# Fastino_FPGA.net
KiCad netlist of a schematic drawn in Altium Designer
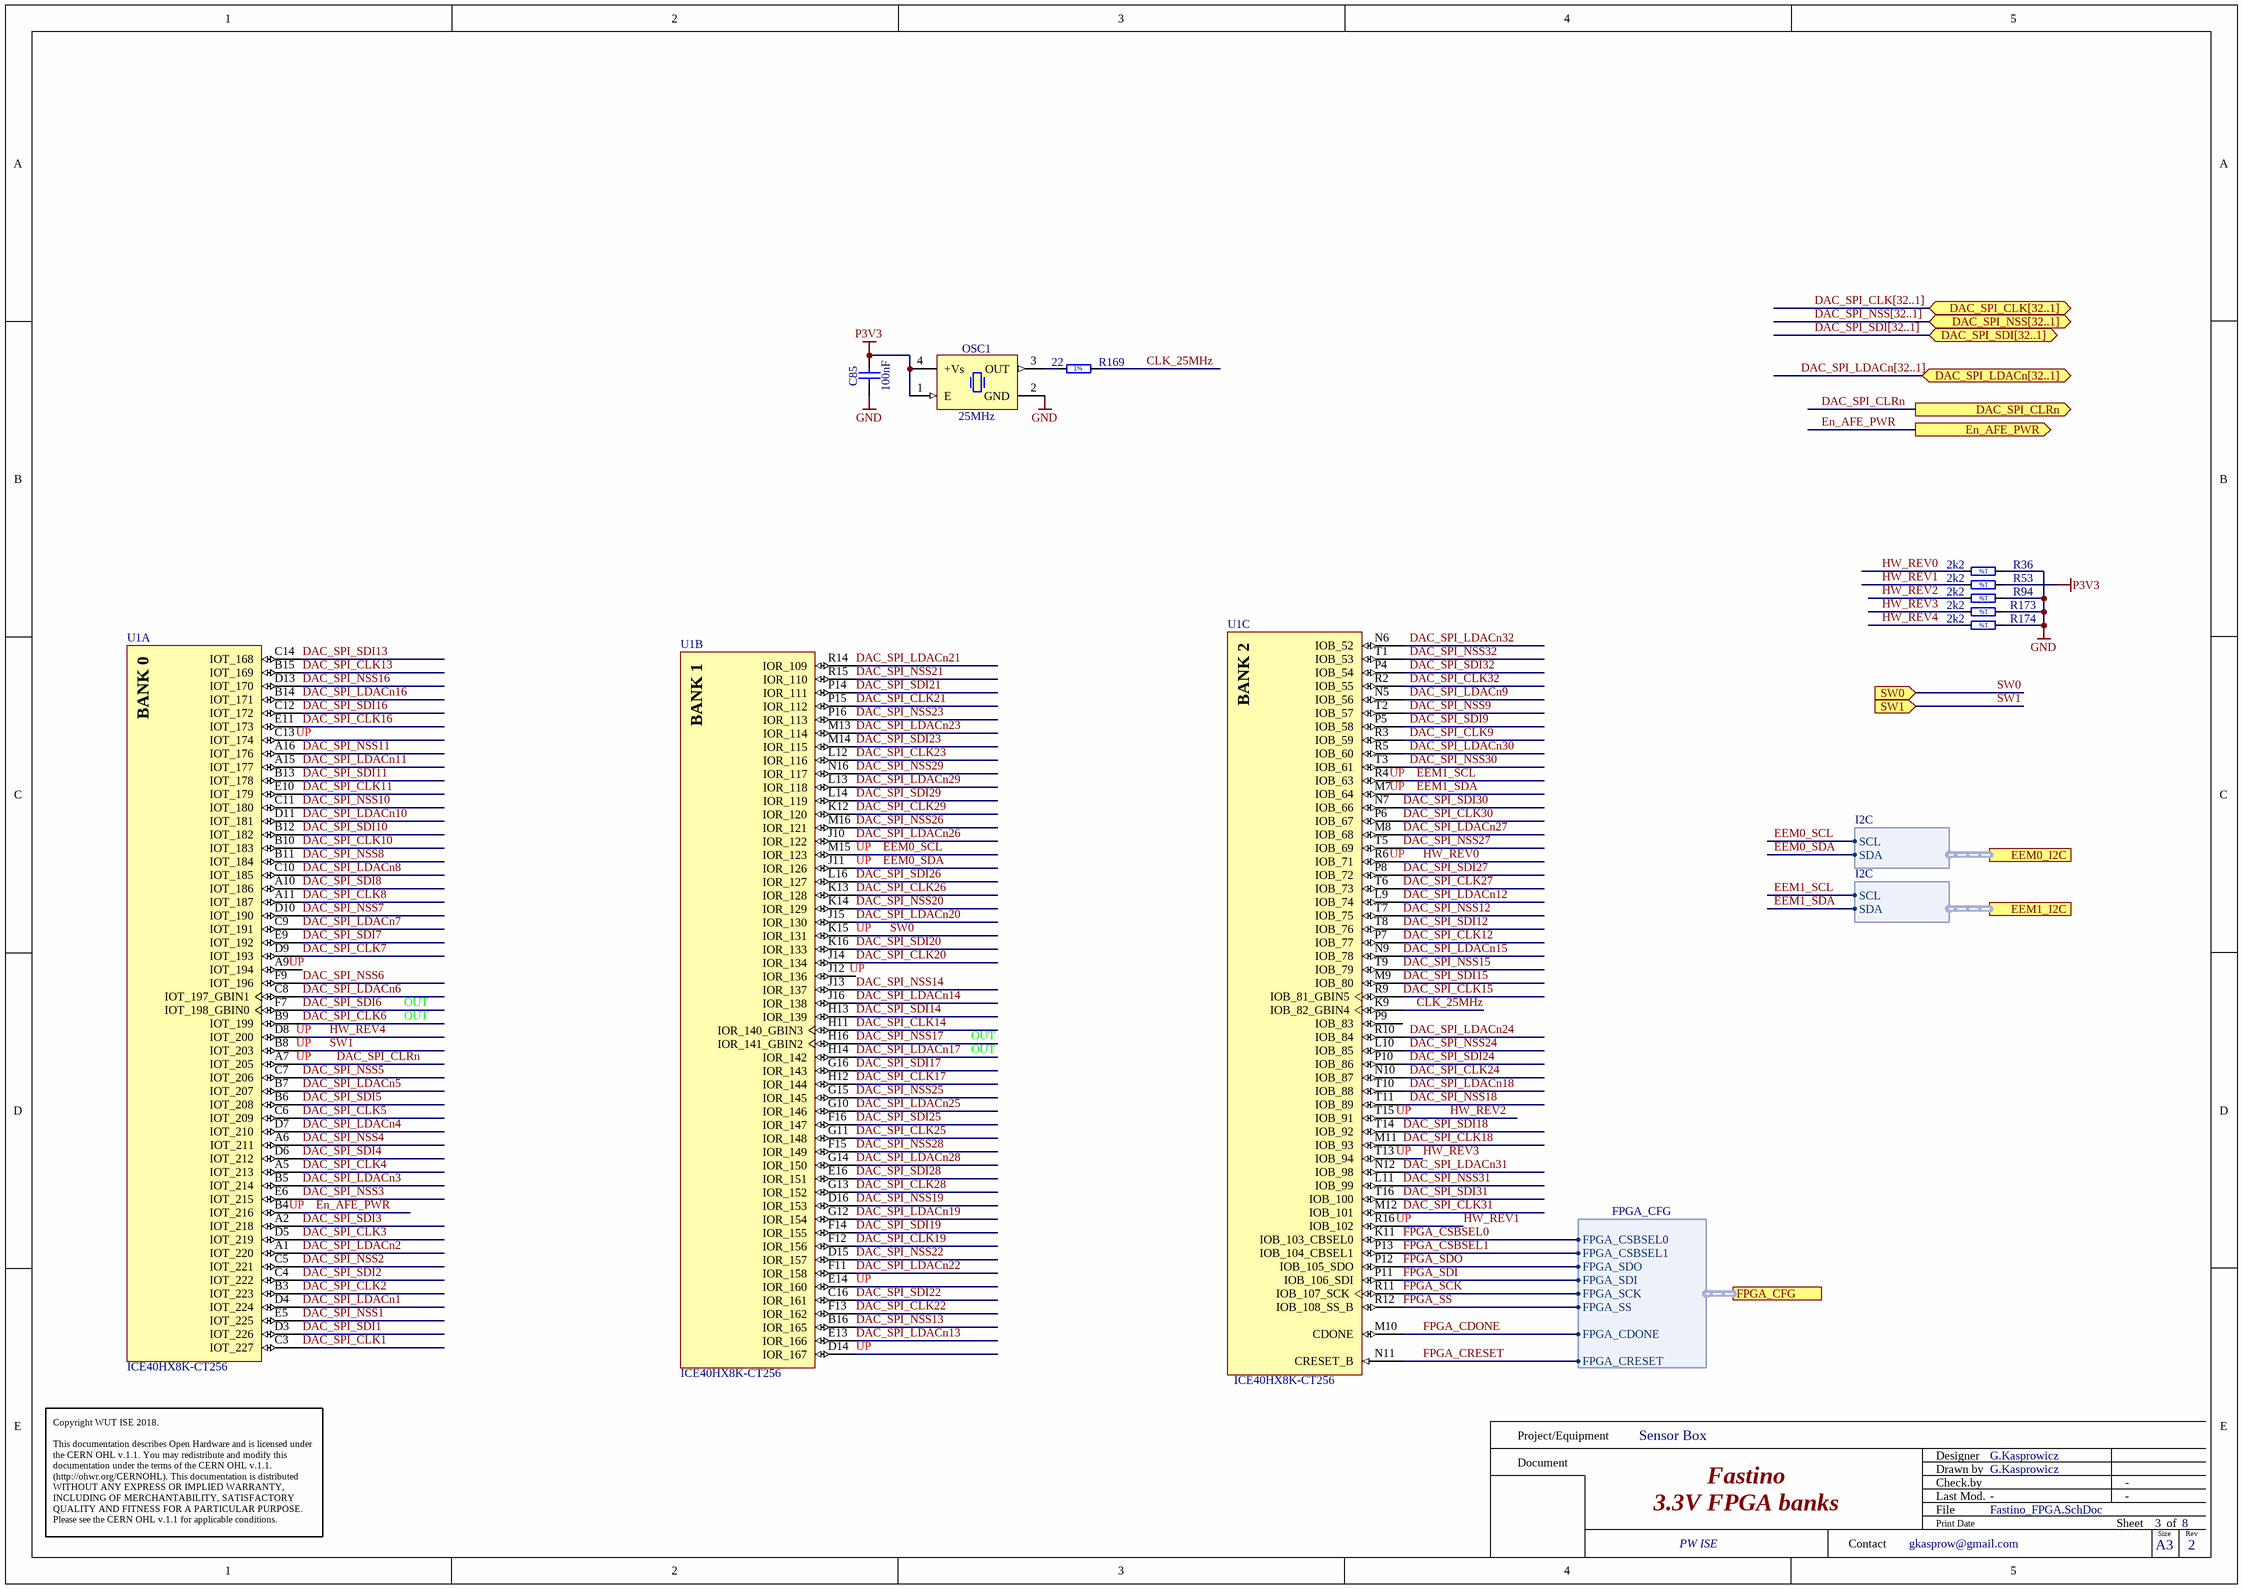
[diagram p0: Fastino_FPGA.SchDoc]

(export (version "E")
  (design (tool "Eeschema 10.0.6"))
  (components
    (comp (ref "C85")
      (value "100nF")
      (footprint "CAPC1005X55N")
      (description "Non-polarised capacitor")
      (fields
        (field (name "PART NUMBER") "CC0402_100NF_16V_10%_X5R")
        (field (name "VOLTAGE") "16V")
        (field (name "AUTHOR") "CERN DEM JLC")
      )
      (libsource (lib "Capacitors") (part "Capacitor - non polarized"))
    )
    (comp (ref "OSC1")
      (value "25MHz")
      (footprint "OSC_IQD_CFPS-39")
      (description "Oscillator 4 pins 1=E 2=GND 3=OUT 4=+Vs")
      (fields
        (field (name "PART NUMBER") "OSC_25MHZ_IQD_LFSPXO025165")
        (field (name "MANUFACTURER") "IQD FREQUENCY PRODUCTS")
        (field (name "AUTHOR") "CERN DEM JLC")
      )
      (libsource (lib "ICs And Semiconductors") (part "Oscillator 1E 2GND 3OUT 4Vs"))
    )
    (comp (ref "R36")
      (value "2k2")
      (footprint "RESC1005X40N")
      (description "Resistor - 1%")
      (fields
        (field (name "PART NUMBER") "R0402_2K2_1%_0.0625W_100PPM")
        (field (name "POWER") "0.0625W")
        (field (name "AUTHOR") "CERN DEM JLC")
      )
      (libsource (lib "Resistors") (part "Resistor - 1%"))
    )
    (comp (ref "R53")
      (value "2k2")
      (footprint "RESC1005X40N")
      (description "Resistor - 1%")
      (fields
        (field (name "PART NUMBER") "R0402_2K2_1%_0.0625W_100PPM")
        (field (name "POWER") "0.0625W")
        (field (name "AUTHOR") "CERN DEM JLC")
      )
      (libsource (lib "Resistors") (part "Resistor - 1%"))
    )
    (comp (ref "R94")
      (value "2k2")
      (footprint "RESC1005X40N")
      (description "Resistor - 1%")
      (fields
        (field (name "PART NUMBER") "R0402_2K2_1%_0.0625W_100PPM")
        (field (name "POWER") "0.0625W")
        (field (name "AUTHOR") "CERN DEM JLC")
      )
      (libsource (lib "Resistors") (part "Resistor - 1%"))
    )
    (comp (ref "R169")
      (value "22")
      (footprint "RESC1005X40N")
      (description "Resistor - 1%")
      (fields
        (field (name "PART NUMBER") "R0402_22R_1%_0.0625W_100PPM")
        (field (name "POWER") "0.0625W")
        (field (name "AUTHOR") "CERN DEM JLC")
      )
      (libsource (lib "Resistors") (part "Resistor - 1%"))
    )
    (comp (ref "R173")
      (value "2k2")
      (footprint "RESC1005X40N")
      (description "Resistor - 1%")
      (fields
        (field (name "PART NUMBER") "R0402_2K2_1%_0.0625W_100PPM")
        (field (name "POWER") "0.0625W")
        (field (name "AUTHOR") "CERN DEM JLC")
      )
      (libsource (lib "Resistors") (part "Resistor - 1%"))
    )
    (comp (ref "R174")
      (value "2k2")
      (footprint "RESC1005X40N")
      (description "Resistor - 1%")
      (fields
        (field (name "PART NUMBER") "R0402_2K2_1%_0.0625W_100PPM")
        (field (name "POWER") "0.0625W")
        (field (name "AUTHOR") "CERN DEM JLC")
      )
      (libsource (lib "Resistors") (part "Resistor - 1%"))
    )
    (comp (ref "U1")
      (value "ICE40HX8K-CT256")
      (footprint "LATC-caBGA-256")
      (fields (field (name "MANUFACTURER") "Lattice Semiconductor"))
      (libsource (lib "Altium Content Vault") (part "LATC-HX8K-caBGA-256"))
    )
  )
  (nets
    (net (code "3") (name "/CLK_25MHz") (class "Default")
      (node (ref "R169") (pin "2") (pinfunction "2_2") (pintype "passive"))
      (node (ref "U1") (pin "K9") (pinfunction "IOB_82_GBIN4_K9") (pintype "bidirectional"))
    )
    (net (code "4") (name "/DAC_SPI_CLK1") (class "Default")
      (node (ref "U1") (pin "C3") (pinfunction "IOT_227_C3") (pintype "bidirectional"))
    )
    (net (code "5") (name "/DAC_SPI_CLK2") (class "Default")
      (node (ref "U1") (pin "B3") (pinfunction "IOT_223_B3") (pintype "bidirectional"))
    )
    (net (code "6") (name "/DAC_SPI_CLK3") (class "Default")
      (node (ref "U1") (pin "D5") (pinfunction "IOT_219_D5") (pintype "bidirectional"))
    )
    (net (code "7") (name "/DAC_SPI_CLK4") (class "Default")
      (node (ref "U1") (pin "A5") (pinfunction "IOT_213_A5") (pintype "bidirectional"))
    )
    (net (code "8") (name "/DAC_SPI_CLK5") (class "Default")
      (node (ref "U1") (pin "C6") (pinfunction "IOT_209_C6") (pintype "bidirectional"))
    )
    (net (code "9") (name "/DAC_SPI_CLK6") (class "Default")
      (node (ref "U1") (pin "B9") (pinfunction "IOT_199_B9") (pintype "bidirectional"))
    )
    (net (code "10") (name "/DAC_SPI_CLK7") (class "Default")
      (node (ref "U1") (pin "D9") (pinfunction "IOT_193_D9") (pintype "bidirectional"))
    )
    (net (code "11") (name "/DAC_SPI_CLK8") (class "Default")
      (node (ref "U1") (pin "A11") (pinfunction "IOT_187_A11") (pintype "bidirectional"))
    )
    (net (code "12") (name "/DAC_SPI_CLK9") (class "Default")
      (node (ref "U1") (pin "R3") (pinfunction "IOB_59_R3") (pintype "bidirectional"))
    )
    (net (code "13") (name "/DAC_SPI_CLK10") (class "Default")
      (node (ref "U1") (pin "B10") (pinfunction "IOT_183_B10") (pintype "bidirectional"))
    )
    (net (code "14") (name "/DAC_SPI_CLK11") (class "Default")
      (node (ref "U1") (pin "E10") (pinfunction "IOT_179_E10") (pintype "bidirectional"))
    )
    (net (code "15") (name "/DAC_SPI_CLK12") (class "Default")
      (node (ref "U1") (pin "P7") (pinfunction "IOB_77_P7") (pintype "bidirectional"))
    )
    (net (code "16") (name "/DAC_SPI_CLK13") (class "Default")
      (node (ref "U1") (pin "B15") (pinfunction "IOT_169_B15") (pintype "bidirectional"))
    )
    (net (code "17") (name "/DAC_SPI_CLK14") (class "Default")
      (node (ref "U1") (pin "H11") (pinfunction "IOR_140_GBIN3_H11") (pintype "bidirectional"))
    )
    (net (code "18") (name "/DAC_SPI_CLK15") (class "Default")
      (node (ref "U1") (pin "R9") (pinfunction "IOB_81_GBIN5_R9") (pintype "bidirectional"))
    )
    (net (code "19") (name "/DAC_SPI_CLK16") (class "Default")
      (node (ref "U1") (pin "E11") (pinfunction "IOT_173_E11") (pintype "bidirectional"))
    )
    (net (code "20") (name "/DAC_SPI_CLK17") (class "Default")
      (node (ref "U1") (pin "H12") (pinfunction "IOR_144_H12") (pintype "bidirectional"))
    )
    (net (code "21") (name "/DAC_SPI_CLK18") (class "Default")
      (node (ref "U1") (pin "M11") (pinfunction "IOB_93_M11") (pintype "bidirectional"))
    )
    (net (code "22") (name "/DAC_SPI_CLK19") (class "Default")
      (node (ref "U1") (pin "F12") (pinfunction "IOR_156_F12") (pintype "bidirectional"))
    )
    (net (code "23") (name "/DAC_SPI_CLK20") (class "Default")
      (node (ref "U1") (pin "J14") (pinfunction "IOR_134_J14") (pintype "bidirectional"))
    )
    (net (code "24") (name "/DAC_SPI_CLK21") (class "Default")
      (node (ref "U1") (pin "P15") (pinfunction "IOR_112_P15") (pintype "bidirectional"))
    )
    (net (code "25") (name "/DAC_SPI_CLK22") (class "Default")
      (node (ref "U1") (pin "F13") (pinfunction "IOR_162_F13") (pintype "bidirectional"))
    )
    (net (code "26") (name "/DAC_SPI_CLK23") (class "Default")
      (node (ref "U1") (pin "L12") (pinfunction "IOR_116_L12") (pintype "bidirectional"))
    )
    (net (code "27") (name "/DAC_SPI_CLK24") (class "Default")
      (node (ref "U1") (pin "N10") (pinfunction "IOB_87_N10") (pintype "bidirectional"))
    )
    (net (code "28") (name "/DAC_SPI_CLK25") (class "Default")
      (node (ref "U1") (pin "G11") (pinfunction "IOR_148_G11") (pintype "bidirectional"))
    )
    (net (code "29") (name "/DAC_SPI_CLK26") (class "Default")
      (node (ref "U1") (pin "K13") (pinfunction "IOR_128_K13") (pintype "bidirectional"))
    )
    (net (code "30") (name "/DAC_SPI_CLK27") (class "Default")
      (node (ref "U1") (pin "T6") (pinfunction "IOB_73_T6") (pintype "bidirectional"))
    )
    (net (code "31") (name "/DAC_SPI_CLK28") (class "Default")
      (node (ref "U1") (pin "G13") (pinfunction "IOR_152_G13") (pintype "bidirectional"))
    )
    (net (code "32") (name "/DAC_SPI_CLK29") (class "Default")
      (node (ref "U1") (pin "K12") (pinfunction "IOR_120_K12") (pintype "bidirectional"))
    )
    (net (code "33") (name "/DAC_SPI_CLK30") (class "Default")
      (node (ref "U1") (pin "P6") (pinfunction "IOB_67_P6") (pintype "bidirectional"))
    )
    (net (code "34") (name "/DAC_SPI_CLK31") (class "Default")
      (node (ref "U1") (pin "M12") (pinfunction "IOB_101_M12") (pintype "bidirectional"))
    )
    (net (code "35") (name "/DAC_SPI_CLK32") (class "Default")
      (node (ref "U1") (pin "R2") (pinfunction "IOB_55_R2") (pintype "bidirectional"))
    )
    (net (code "37") (name "/DAC_SPI_CLRn") (class "Default")
      (node (ref "U1") (pin "A7") (pinfunction "IOT_205_A7") (pintype "bidirectional"))
    )
    (net (code "38") (name "/DAC_SPI_LDACn1") (class "Default")
      (node (ref "U1") (pin "D4") (pinfunction "IOT_224_D4") (pintype "bidirectional"))
    )
    (net (code "39") (name "/DAC_SPI_LDACn2") (class "Default")
      (node (ref "U1") (pin "A1") (pinfunction "IOT_220_A1") (pintype "bidirectional"))
    )
    (net (code "40") (name "/DAC_SPI_LDACn3") (class "Default")
      (node (ref "U1") (pin "B5") (pinfunction "IOT_214_B5") (pintype "bidirectional"))
    )
    (net (code "41") (name "/DAC_SPI_LDACn4") (class "Default")
      (node (ref "U1") (pin "D7") (pinfunction "IOT_210_D7") (pintype "bidirectional"))
    )
    (net (code "42") (name "/DAC_SPI_LDACn5") (class "Default")
      (node (ref "U1") (pin "B7") (pinfunction "IOT_207_B7") (pintype "bidirectional"))
    )
    (net (code "43") (name "/DAC_SPI_LDACn6") (class "Default")
      (node (ref "U1") (pin "C8") (pinfunction "IOT_197_GBIN1_C8") (pintype "bidirectional"))
    )
    (net (code "44") (name "/DAC_SPI_LDACn7") (class "Default")
      (node (ref "U1") (pin "C9") (pinfunction "IOT_191_C9") (pintype "bidirectional"))
    )
    (net (code "45") (name "/DAC_SPI_LDACn8") (class "Default")
      (node (ref "U1") (pin "C10") (pinfunction "IOT_185_C10") (pintype "bidirectional"))
    )
    (net (code "46") (name "/DAC_SPI_LDACn9") (class "Default")
      (node (ref "U1") (pin "N5") (pinfunction "IOB_56_N5") (pintype "bidirectional"))
    )
    (net (code "47") (name "/DAC_SPI_LDACn10") (class "Default")
      (node (ref "U1") (pin "D11") (pinfunction "IOT_181_D11") (pintype "bidirectional"))
    )
    (net (code "48") (name "/DAC_SPI_LDACn11") (class "Default")
      (node (ref "U1") (pin "A15") (pinfunction "IOT_177_A15") (pintype "bidirectional"))
    )
    (net (code "49") (name "/DAC_SPI_LDACn12") (class "Default")
      (node (ref "U1") (pin "L9") (pinfunction "IOB_74_L9") (pintype "bidirectional"))
    )
    (net (code "50") (name "/DAC_SPI_LDACn13") (class "Default")
      (node (ref "U1") (pin "E13") (pinfunction "IOR_166_E13") (pintype "bidirectional"))
    )
    (net (code "51") (name "/DAC_SPI_LDACn14") (class "Default")
      (node (ref "U1") (pin "J16") (pinfunction "IOR_138_J16") (pintype "bidirectional"))
    )
    (net (code "52") (name "/DAC_SPI_LDACn15") (class "Default")
      (node (ref "U1") (pin "N9") (pinfunction "IOB_78_N9") (pintype "bidirectional"))
    )
    (net (code "53") (name "/DAC_SPI_LDACn16") (class "Default")
      (node (ref "U1") (pin "B14") (pinfunction "IOT_171_B14") (pintype "bidirectional"))
    )
    (net (code "54") (name "/DAC_SPI_LDACn17") (class "Default")
      (node (ref "U1") (pin "H14") (pinfunction "IOR_142_H14") (pintype "bidirectional"))
    )
    (net (code "55") (name "/DAC_SPI_LDACn18") (class "Default")
      (node (ref "U1") (pin "T10") (pinfunction "IOB_88_T10") (pintype "bidirectional"))
    )
    (net (code "56") (name "/DAC_SPI_LDACn19") (class "Default")
      (node (ref "U1") (pin "G12") (pinfunction "IOR_154_G12") (pintype "bidirectional"))
    )
    (net (code "57") (name "/DAC_SPI_LDACn20") (class "Default")
      (node (ref "U1") (pin "J15") (pinfunction "IOR_130_J15") (pintype "bidirectional"))
    )
    (net (code "58") (name "/DAC_SPI_LDACn21") (class "Default")
      (node (ref "U1") (pin "R14") (pinfunction "IOR_109_R14") (pintype "bidirectional"))
    )
    (net (code "59") (name "/DAC_SPI_LDACn22") (class "Default")
      (node (ref "U1") (pin "F11") (pinfunction "IOR_158_F11") (pintype "bidirectional"))
    )
    (net (code "60") (name "/DAC_SPI_LDACn23") (class "Default")
      (node (ref "U1") (pin "M13") (pinfunction "IOR_114_M13") (pintype "bidirectional"))
    )
    (net (code "61") (name "/DAC_SPI_LDACn24") (class "Default")
      (node (ref "U1") (pin "R10") (pinfunction "IOB_84_R10") (pintype "bidirectional"))
    )
    (net (code "62") (name "/DAC_SPI_LDACn25") (class "Default")
      (node (ref "U1") (pin "G10") (pinfunction "IOR_146_G10") (pintype "bidirectional"))
    )
    (net (code "63") (name "/DAC_SPI_LDACn26") (class "Default")
      (node (ref "U1") (pin "J10") (pinfunction "IOR_122_J10") (pintype "bidirectional"))
    )
    (net (code "64") (name "/DAC_SPI_LDACn27") (class "Default")
      (node (ref "U1") (pin "M8") (pinfunction "IOB_68_M8") (pintype "bidirectional"))
    )
    (net (code "65") (name "/DAC_SPI_LDACn28") (class "Default")
      (node (ref "U1") (pin "G14") (pinfunction "IOR_150_G14") (pintype "bidirectional"))
    )
    (net (code "66") (name "/DAC_SPI_LDACn29") (class "Default")
      (node (ref "U1") (pin "L13") (pinfunction "IOR_118_L13") (pintype "bidirectional"))
    )
    (net (code "67") (name "/DAC_SPI_LDACn30") (class "Default")
      (node (ref "U1") (pin "R5") (pinfunction "IOB_60_R5") (pintype "bidirectional"))
    )
    (net (code "68") (name "/DAC_SPI_LDACn31") (class "Default")
      (node (ref "U1") (pin "N12") (pinfunction "IOB_98_N12") (pintype "bidirectional"))
    )
    (net (code "69") (name "/DAC_SPI_LDACn32") (class "Default")
      (node (ref "U1") (pin "N6") (pinfunction "IOB_52_N6") (pintype "bidirectional"))
    )
    (net (code "71") (name "/DAC_SPI_NSS1") (class "Default")
      (node (ref "U1") (pin "E5") (pinfunction "IOT_225_E5") (pintype "bidirectional"))
    )
    (net (code "72") (name "/DAC_SPI_NSS2") (class "Default")
      (node (ref "U1") (pin "C5") (pinfunction "IOT_221_C5") (pintype "bidirectional"))
    )
    (net (code "73") (name "/DAC_SPI_NSS3") (class "Default")
      (node (ref "U1") (pin "E6") (pinfunction "IOT_215_E6") (pintype "bidirectional"))
    )
    (net (code "74") (name "/DAC_SPI_NSS4") (class "Default")
      (node (ref "U1") (pin "A6") (pinfunction "IOT_211_A6") (pintype "bidirectional"))
    )
    (net (code "75") (name "/DAC_SPI_NSS5") (class "Default")
      (node (ref "U1") (pin "C7") (pinfunction "IOT_206_C7") (pintype "bidirectional"))
    )
    (net (code "76") (name "/DAC_SPI_NSS6") (class "Default")
      (node (ref "U1") (pin "F9") (pinfunction "IOT_196_F9") (pintype "bidirectional"))
    )
    (net (code "77") (name "/DAC_SPI_NSS7") (class "Default")
      (node (ref "U1") (pin "D10") (pinfunction "IOT_190_D10") (pintype "bidirectional"))
    )
    (net (code "78") (name "/DAC_SPI_NSS8") (class "Default")
      (node (ref "U1") (pin "B11") (pinfunction "IOT_184_B11") (pintype "bidirectional"))
    )
    (net (code "79") (name "/DAC_SPI_NSS9") (class "Default")
      (node (ref "U1") (pin "T2") (pinfunction "IOB_57_T2") (pintype "bidirectional"))
    )
    (net (code "80") (name "/DAC_SPI_NSS10") (class "Default")
      (node (ref "U1") (pin "C11") (pinfunction "IOT_180_C11") (pintype "bidirectional"))
    )
    (net (code "81") (name "/DAC_SPI_NSS11") (class "Default")
      (node (ref "U1") (pin "A16") (pinfunction "IOT_176_A16") (pintype "bidirectional"))
    )
    (net (code "82") (name "/DAC_SPI_NSS12") (class "Default")
      (node (ref "U1") (pin "T7") (pinfunction "IOB_75_T7") (pintype "bidirectional"))
    )
    (net (code "83") (name "/DAC_SPI_NSS13") (class "Default")
      (node (ref "U1") (pin "B16") (pinfunction "IOR_165_B16") (pintype "bidirectional"))
    )
    (net (code "84") (name "/DAC_SPI_NSS14") (class "Default")
      (node (ref "U1") (pin "J13") (pinfunction "IOR_137_J13") (pintype "bidirectional"))
    )
    (net (code "85") (name "/DAC_SPI_NSS15") (class "Default")
      (node (ref "U1") (pin "T9") (pinfunction "IOB_79_T9") (pintype "bidirectional"))
    )
    (net (code "86") (name "/DAC_SPI_NSS16") (class "Default")
      (node (ref "U1") (pin "D13") (pinfunction "IOT_170_D13") (pintype "bidirectional"))
    )
    (net (code "87") (name "/DAC_SPI_NSS17") (class "Default")
      (node (ref "U1") (pin "H16") (pinfunction "IOR_141_GBIN2_H16") (pintype "bidirectional"))
    )
    (net (code "88") (name "/DAC_SPI_NSS18") (class "Default")
      (node (ref "U1") (pin "T11") (pinfunction "IOB_89_T11") (pintype "bidirectional"))
    )
    (net (code "89") (name "/DAC_SPI_NSS19") (class "Default")
      (node (ref "U1") (pin "D16") (pinfunction "IOR_153_D16") (pintype "bidirectional"))
    )
    (net (code "90") (name "/DAC_SPI_NSS20") (class "Default")
      (node (ref "U1") (pin "K14") (pinfunction "IOR_129_K14") (pintype "bidirectional"))
    )
    (net (code "91") (name "/DAC_SPI_NSS21") (class "Default")
      (node (ref "U1") (pin "R15") (pinfunction "IOR_110_R15") (pintype "bidirectional"))
    )
    (net (code "92") (name "/DAC_SPI_NSS22") (class "Default")
      (node (ref "U1") (pin "D15") (pinfunction "IOR_157_D15") (pintype "bidirectional"))
    )
    (net (code "93") (name "/DAC_SPI_NSS23") (class "Default")
      (node (ref "U1") (pin "P16") (pinfunction "IOR_113_P16") (pintype "bidirectional"))
    )
    (net (code "94") (name "/DAC_SPI_NSS24") (class "Default")
      (node (ref "U1") (pin "L10") (pinfunction "IOB_85_L10") (pintype "bidirectional"))
    )
    (net (code "95") (name "/DAC_SPI_NSS25") (class "Default")
      (node (ref "U1") (pin "G15") (pinfunction "IOR_145_G15") (pintype "bidirectional"))
    )
    (net (code "96") (name "/DAC_SPI_NSS26") (class "Default")
      (node (ref "U1") (pin "M16") (pinfunction "IOR_121_M16") (pintype "bidirectional"))
    )
    (net (code "97") (name "/DAC_SPI_NSS27") (class "Default")
      (node (ref "U1") (pin "T5") (pinfunction "IOB_69_T5") (pintype "bidirectional"))
    )
    (net (code "98") (name "/DAC_SPI_NSS28") (class "Default")
      (node (ref "U1") (pin "F15") (pinfunction "IOR_149_F15") (pintype "bidirectional"))
    )
    (net (code "99") (name "/DAC_SPI_NSS29") (class "Default")
      (node (ref "U1") (pin "N16") (pinfunction "IOR_117_N16") (pintype "bidirectional"))
    )
    (net (code "100") (name "/DAC_SPI_NSS30") (class "Default")
      (node (ref "U1") (pin "T3") (pinfunction "IOB_61_T3") (pintype "bidirectional"))
    )
    (net (code "101") (name "/DAC_SPI_NSS31") (class "Default")
      (node (ref "U1") (pin "L11") (pinfunction "IOB_99_L11") (pintype "bidirectional"))
    )
    (net (code "102") (name "/DAC_SPI_NSS32") (class "Default")
      (node (ref "U1") (pin "T1") (pinfunction "IOB_53_T1") (pintype "bidirectional"))
    )
    (net (code "104") (name "/DAC_SPI_SDI1") (class "Default")
      (node (ref "U1") (pin "D3") (pinfunction "IOT_226_D3") (pintype "bidirectional"))
    )
    (net (code "105") (name "/DAC_SPI_SDI2") (class "Default")
      (node (ref "U1") (pin "C4") (pinfunction "IOT_222_C4") (pintype "bidirectional"))
    )
    (net (code "106") (name "/DAC_SPI_SDI3") (class "Default")
      (node (ref "U1") (pin "A2") (pinfunction "IOT_218_A2") (pintype "bidirectional"))
    )
    (net (code "107") (name "/DAC_SPI_SDI4") (class "Default")
      (node (ref "U1") (pin "D6") (pinfunction "IOT_212_D6") (pintype "bidirectional"))
    )
    (net (code "108") (name "/DAC_SPI_SDI5") (class "Default")
      (node (ref "U1") (pin "B6") (pinfunction "IOT_208_B6") (pintype "bidirectional"))
    )
    (net (code "109") (name "/DAC_SPI_SDI6") (class "Default")
      (node (ref "U1") (pin "F7") (pinfunction "IOT_198_GBIN0_F7") (pintype "bidirectional"))
    )
    (net (code "110") (name "/DAC_SPI_SDI7") (class "Default")
      (node (ref "U1") (pin "E9") (pinfunction "IOT_192_E9") (pintype "bidirectional"))
    )
    (net (code "111") (name "/DAC_SPI_SDI8") (class "Default")
      (node (ref "U1") (pin "A10") (pinfunction "IOT_186_A10") (pintype "bidirectional"))
    )
    (net (code "112") (name "/DAC_SPI_SDI9") (class "Default")
      (node (ref "U1") (pin "P5") (pinfunction "IOB_58_P5") (pintype "bidirectional"))
    )
    (net (code "113") (name "/DAC_SPI_SDI10") (class "Default")
      (node (ref "U1") (pin "B12") (pinfunction "IOT_182_B12") (pintype "bidirectional"))
    )
    (net (code "114") (name "/DAC_SPI_SDI11") (class "Default")
      (node (ref "U1") (pin "B13") (pinfunction "IOT_178_B13") (pintype "bidirectional"))
    )
    (net (code "115") (name "/DAC_SPI_SDI12") (class "Default")
      (node (ref "U1") (pin "T8") (pinfunction "IOB_76_T8") (pintype "bidirectional"))
    )
    (net (code "116") (name "/DAC_SPI_SDI13") (class "Default")
      (node (ref "U1") (pin "C14") (pinfunction "IOT_168_C14") (pintype "bidirectional"))
    )
    (net (code "117") (name "/DAC_SPI_SDI14") (class "Default")
      (node (ref "U1") (pin "H13") (pinfunction "IOR_139_H13") (pintype "bidirectional"))
    )
    (net (code "118") (name "/DAC_SPI_SDI15") (class "Default")
      (node (ref "U1") (pin "M9") (pinfunction "IOB_80_M9") (pintype "bidirectional"))
    )
    (net (code "119") (name "/DAC_SPI_SDI16") (class "Default")
      (node (ref "U1") (pin "C12") (pinfunction "IOT_172_C12") (pintype "bidirectional"))
    )
    (net (code "120") (name "/DAC_SPI_SDI17") (class "Default")
      (node (ref "U1") (pin "G16") (pinfunction "IOR_143_G16") (pintype "bidirectional"))
    )
    (net (code "121") (name "/DAC_SPI_SDI18") (class "Default")
      (node (ref "U1") (pin "T14") (pinfunction "IOB_92_T14") (pintype "bidirectional"))
    )
    (net (code "122") (name "/DAC_SPI_SDI19") (class "Default")
      (node (ref "U1") (pin "F14") (pinfunction "IOR_155_F14") (pintype "bidirectional"))
    )
    (net (code "123") (name "/DAC_SPI_SDI20") (class "Default")
      (node (ref "U1") (pin "K16") (pinfunction "IOR_133_K16") (pintype "bidirectional"))
    )
    (net (code "124") (name "/DAC_SPI_SDI21") (class "Default")
      (node (ref "U1") (pin "P14") (pinfunction "IOR_111_P14") (pintype "bidirectional"))
    )
    (net (code "125") (name "/DAC_SPI_SDI22") (class "Default")
      (node (ref "U1") (pin "C16") (pinfunction "IOR_161_C16") (pintype "bidirectional"))
    )
    (net (code "126") (name "/DAC_SPI_SDI23") (class "Default")
      (node (ref "U1") (pin "M14") (pinfunction "IOR_115_M14") (pintype "bidirectional"))
    )
    (net (code "127") (name "/DAC_SPI_SDI24") (class "Default")
      (node (ref "U1") (pin "P10") (pinfunction "IOB_86_P10") (pintype "bidirectional"))
    )
    (net (code "128") (name "/DAC_SPI_SDI25") (class "Default")
      (node (ref "U1") (pin "F16") (pinfunction "IOR_147_F16") (pintype "bidirectional"))
    )
    (net (code "129") (name "/DAC_SPI_SDI26") (class "Default")
      (node (ref "U1") (pin "L16") (pinfunction "IOR_127_L16") (pintype "bidirectional"))
    )
    (net (code "130") (name "/DAC_SPI_SDI27") (class "Default")
      (node (ref "U1") (pin "P8") (pinfunction "IOB_72_P8") (pintype "bidirectional"))
    )
    (net (code "131") (name "/DAC_SPI_SDI28") (class "Default")
      (node (ref "U1") (pin "E16") (pinfunction "IOR_151_E16") (pintype "bidirectional"))
    )
    (net (code "132") (name "/DAC_SPI_SDI29") (class "Default")
      (node (ref "U1") (pin "L14") (pinfunction "IOR_119_L14") (pintype "bidirectional"))
    )
    (net (code "133") (name "/DAC_SPI_SDI30") (class "Default")
      (node (ref "U1") (pin "N7") (pinfunction "IOB_66_N7") (pintype "bidirectional"))
    )
    (net (code "134") (name "/DAC_SPI_SDI31") (class "Default")
      (node (ref "U1") (pin "T16") (pinfunction "IOB_100_T16") (pintype "bidirectional"))
    )
    (net (code "135") (name "/DAC_SPI_SDI32") (class "Default")
      (node (ref "U1") (pin "P4") (pinfunction "IOB_54_P4") (pintype "bidirectional"))
    )
    (net (code "137") (name "/EEM0_SCL") (class "Default")
      (node (ref "U1") (pin "M15") (pinfunction "IOR_123_M15") (pintype "bidirectional"))
    )
    (net (code "138") (name "/EEM0_SDA") (class "Default")
      (node (ref "U1") (pin "J11") (pinfunction "IOR_126_J11") (pintype "bidirectional"))
    )
    (net (code "139") (name "/EEM1_SCL") (class "Default")
      (node (ref "U1") (pin "R4") (pinfunction "IOB_63_R4") (pintype "bidirectional"))
    )
    (net (code "140") (name "/EEM1_SDA") (class "Default")
      (node (ref "U1") (pin "M7") (pinfunction "IOB_64_M7") (pintype "bidirectional"))
    )
    (net (code "141") (name "/En_AFE_PWR") (class "Default")
      (node (ref "U1") (pin "B4") (pinfunction "IOT_216_B4") (pintype "bidirectional"))
    )
    (net (code "142") (name "/FPGA_CDONE") (class "Default")
      (node (ref "U1") (pin "M10") (pinfunction "CDONE_M10") (pintype "bidirectional"))
    )
    (net (code "143") (name "/FPGA_CRESET") (class "Default")
      (node (ref "U1") (pin "N11") (pinfunction "CRESET_B_N11") (pintype "input"))
    )
    (net (code "144") (name "/FPGA_CSBSEL0") (class "Default")
      (node (ref "U1") (pin "K11") (pinfunction "IOB_103_CBSEL0_K11") (pintype "bidirectional"))
    )
    (net (code "145") (name "/FPGA_CSBSEL1") (class "Default")
      (node (ref "U1") (pin "P13") (pinfunction "IOB_104_CBSEL1_P13") (pintype "bidirectional"))
    )
    (net (code "146") (name "/FPGA_SCK") (class "Default")
      (node (ref "U1") (pin "R11") (pinfunction "IOB_107_SCK_R11") (pintype "bidirectional"))
    )
    (net (code "147") (name "/FPGA_SDI") (class "Default")
      (node (ref "U1") (pin "P11") (pinfunction "IOB_106_SDI_P11") (pintype "bidirectional"))
    )
    (net (code "148") (name "/FPGA_SDO") (class "Default")
      (node (ref "U1") (pin "P12") (pinfunction "IOB_105_SDO_P12") (pintype "bidirectional"))
    )
    (net (code "149") (name "/FPGA_SS") (class "Default")
      (node (ref "U1") (pin "R12") (pinfunction "IOB_108_SS_B_R12") (pintype "bidirectional"))
    )
    (net (code "150") (name "/HW_REV0") (class "Default")
      (node (ref "R36") (pin "2") (pinfunction "2_2") (pintype "passive"))
      (node (ref "U1") (pin "R6") (pinfunction "IOB_71_R6") (pintype "bidirectional"))
    )
    (net (code "151") (name "/HW_REV1") (class "Default")
      (node (ref "R53") (pin "2") (pinfunction "2_2") (pintype "passive"))
      (node (ref "U1") (pin "R16") (pinfunction "IOB_102_R16") (pintype "bidirectional"))
    )
    (net (code "152") (name "/HW_REV2") (class "Default")
      (node (ref "R94") (pin "2") (pinfunction "2_2") (pintype "passive"))
      (node (ref "U1") (pin "T15") (pinfunction "IOB_91_T15") (pintype "bidirectional"))
    )
    (net (code "153") (name "/HW_REV3") (class "Default")
      (node (ref "R173") (pin "2") (pinfunction "2_2") (pintype "passive"))
      (node (ref "U1") (pin "T13") (pinfunction "IOB_94_T13") (pintype "bidirectional"))
    )
    (net (code "154") (name "/HW_REV4") (class "Default")
      (node (ref "R174") (pin "2") (pinfunction "2_2") (pintype "passive"))
      (node (ref "U1") (pin "D8") (pinfunction "IOT_200_D8") (pintype "bidirectional"))
    )
    (net (code "155") (name "/SW0") (class "Default")
      (node (ref "U1") (pin "K15") (pinfunction "IOR_131_K15") (pintype "bidirectional"))
    )
    (net (code "156") (name "/SW1") (class "Default")
      (node (ref "U1") (pin "B8") (pinfunction "IOT_203_B8") (pintype "bidirectional"))
    )
    (net (code "159") (name "GND") (class "Default")
      (node (ref "C85") (pin "1") (pinfunction "1_1") (pintype "passive"))
      (node (ref "OSC1") (pin "2") (pinfunction "GND_2") (pintype "power_in"))
      (node (ref "R173") (pin "1") (pinfunction "1_1") (pintype "passive"))
      (node (ref "R174") (pin "1") (pinfunction "1_1") (pintype "passive"))
      (node (ref "R36") (pin "1") (pinfunction "1_1") (pintype "passive"))
      (node (ref "R94") (pin "1") (pinfunction "1_1") (pintype "passive"))
    )
    (net (code "160") (name "Net-(OSC1-OUT)") (class "Default")
      (node (ref "OSC1") (pin "3") (pinfunction "OUT_3") (pintype "output"))
      (node (ref "R169") (pin "1") (pinfunction "1_1") (pintype "passive"))
    )
    (net (code "161") (name "P3V3") (class "Default")
      (node (ref "C85") (pin "2") (pinfunction "2_2") (pintype "passive"))
      (node (ref "OSC1") (pin "1") (pinfunction "E_1") (pintype "input"))
      (node (ref "OSC1") (pin "4") (pinfunction "+Vs_4") (pintype "power_in"))
      (node (ref "R53") (pin "1") (pinfunction "1_1") (pintype "passive"))
    )
    (net (code "162") (name "unconnected-(U1A-IOT_174-PadC13)") (class "Default")
      (node (ref "U1") (pin "C13") (pinfunction "IOT_174_C13") (pintype "bidirectional"))
    )
    (net (code "163") (name "unconnected-(U1A-IOT_194-PadA9)") (class "Default")
      (node (ref "U1") (pin "A9") (pinfunction "IOT_194_A9") (pintype "bidirectional"))
    )
    (net (code "164") (name "unconnected-(U1B-IOR_136-PadJ12)") (class "Default")
      (node (ref "U1") (pin "J12") (pinfunction "IOR_136_J12") (pintype "bidirectional"))
    )
    (net (code "165") (name "unconnected-(U1B-IOR_160-PadE14)") (class "Default")
      (node (ref "U1") (pin "E14") (pinfunction "IOR_160_E14") (pintype "bidirectional"))
    )
    (net (code "166") (name "unconnected-(U1B-IOR_167-PadD14)") (class "Default")
      (node (ref "U1") (pin "D14") (pinfunction "IOR_167_D14") (pintype "bidirectional"))
    )
    (net (code "167") (name "unconnected-(U1C-IOB_83-PadP9)") (class "Default")
      (node (ref "U1") (pin "P9") (pinfunction "IOB_83_P9") (pintype "bidirectional"))
    )
  )
)
